# mpiv2.net
KiCad netlist of a schematic drawn in EAGLE
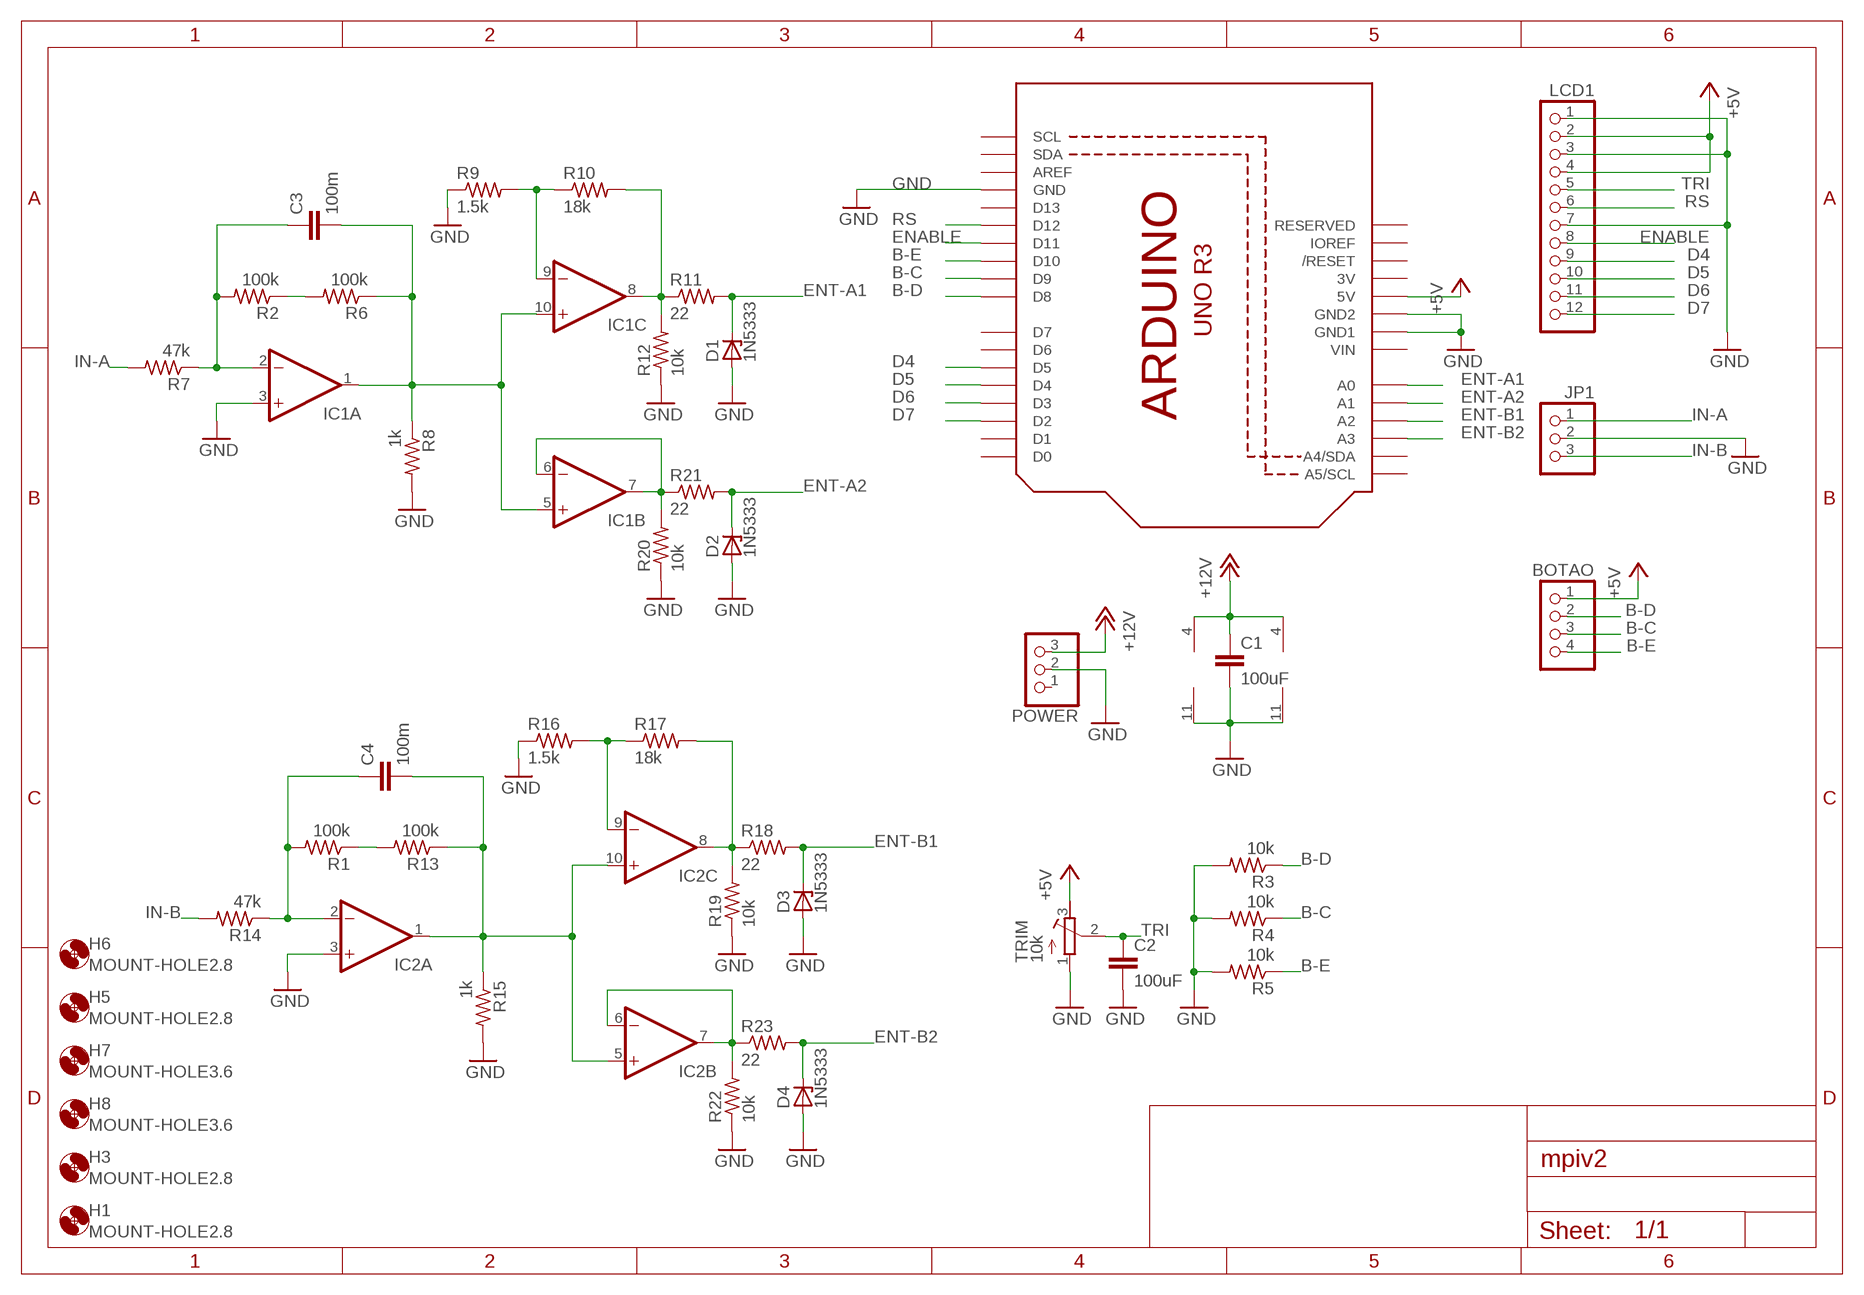
[diagram p0: schematic, sheet 1]

(export (version "E")
  (design (tool "Eeschema 10.0.6"))
  (components
    (comp (ref "BOTAO")
      (value "HEADER-1X4")
      (footprint "eagle-import:1X04_OVAL")
      (libsource (lib "eagle-import") (part "HEADER-1X4"))
    )
    (comp (ref "C1")
      (value "100uF")
      (footprint "eagle-import:C050-035X075")
      (libsource (lib "eagle-import") (part "C-EU050-035X075"))
    )
    (comp (ref "C2")
      (value "100uF")
      (footprint "eagle-import:C050-035X075")
      (libsource (lib "eagle-import") (part "C-EU050-035X075"))
    )
    (comp (ref "C3")
      (value "100m")
      (footprint "eagle-import:C075-032X103")
      (libsource (lib "eagle-import") (part "C-EU075-032X103"))
    )
    (comp (ref "C4")
      (value "100m")
      (footprint "eagle-import:C075-032X103")
      (libsource (lib "eagle-import") (part "C-EU075-032X103"))
    )
    (comp (ref "D1")
      (value "1N5333")
      (footprint "eagle-import:C1702-15")
      (libsource (lib "eagle-import") (part "1N5333"))
    )
    (comp (ref "D2")
      (value "1N5333")
      (footprint "eagle-import:C1702-15")
      (libsource (lib "eagle-import") (part "1N5333"))
    )
    (comp (ref "D3")
      (value "1N5333")
      (footprint "eagle-import:C1702-15")
      (libsource (lib "eagle-import") (part "1N5333"))
    )
    (comp (ref "D4")
      (value "1N5333")
      (footprint "eagle-import:C1702-15")
      (libsource (lib "eagle-import") (part "1N5333"))
    )
    (comp (ref "H1")
      (value "MOUNT-HOLE2.8")
      (footprint "eagle-import:2,8")
      (libsource (lib "eagle-import") (part "MOUNT-HOLE2.8"))
    )
    (comp (ref "H3")
      (value "MOUNT-HOLE2.8")
      (footprint "eagle-import:2,8")
      (libsource (lib "eagle-import") (part "MOUNT-HOLE2.8"))
    )
    (comp (ref "H5")
      (value "MOUNT-HOLE2.8")
      (footprint "eagle-import:2,8")
      (libsource (lib "eagle-import") (part "MOUNT-HOLE2.8"))
    )
    (comp (ref "H6")
      (value "MOUNT-HOLE2.8")
      (footprint "eagle-import:2,8")
      (libsource (lib "eagle-import") (part "MOUNT-HOLE2.8"))
    )
    (comp (ref "H7")
      (value "MOUNT-HOLE3.6")
      (footprint "eagle-import:3,6")
      (libsource (lib "eagle-import") (part "MOUNT-HOLE3.6"))
    )
    (comp (ref "H8")
      (value "MOUNT-HOLE3.6")
      (footprint "eagle-import:3,6")
      (libsource (lib "eagle-import") (part "MOUNT-HOLE3.6"))
    )
    (comp (ref "IC1")
      (value "4AMP_P4+11N")
      (footprint "eagle-import:DIL14")
      (libsource (lib "eagle-import") (part "4AMP_P4+11N"))
    )
    (comp (ref "IC2")
      (value "4AMP_P4+11N")
      (footprint "eagle-import:DIL14")
      (libsource (lib "eagle-import") (part "4AMP_P4+11N"))
    )
    (comp (ref "JP1")
      (value "PINHD-1X3")
      (footprint "eagle-import:1X03")
      (libsource (lib "eagle-import") (part "PINHD-1X3"))
    )
    (comp (ref "LCD1")
      (value "PINHD-1X12")
      (footprint "eagle-import:1X12")
      (libsource (lib "eagle-import") (part "PINHD-1X12"))
    )
    (comp (ref "POWER")
      (value "HEADER-1X3")
      (footprint "eagle-import:1X03_OVAL")
      (libsource (lib "eagle-import") (part "HEADER-1X3"))
    )
    (comp (ref "R1")
      (value "100k")
      (footprint "eagle-import:0207_10")
      (libsource (lib "eagle-import") (part "R-US_0207/10"))
    )
    (comp (ref "R2")
      (value "100k")
      (footprint "eagle-import:0207_10")
      (libsource (lib "eagle-import") (part "R-US_0207/10"))
    )
    (comp (ref "R3")
      (value "10k")
      (footprint "eagle-import:0207_10")
      (libsource (lib "eagle-import") (part "R-US_0207/10"))
    )
    (comp (ref "R4")
      (value "10k")
      (footprint "eagle-import:0207_10")
      (libsource (lib "eagle-import") (part "R-US_0207/10"))
    )
    (comp (ref "R5")
      (value "10k")
      (footprint "eagle-import:0207_10")
      (libsource (lib "eagle-import") (part "R-US_0207/10"))
    )
    (comp (ref "R6")
      (value "100k")
      (footprint "eagle-import:0207_10")
      (libsource (lib "eagle-import") (part "R-US_0207/10"))
    )
    (comp (ref "R7")
      (value "47k")
      (footprint "eagle-import:0207_10")
      (libsource (lib "eagle-import") (part "R-US_0207/10"))
    )
    (comp (ref "R8")
      (value "1k")
      (footprint "eagle-import:0207_10")
      (libsource (lib "eagle-import") (part "R-US_0207/10"))
    )
    (comp (ref "R9")
      (value "1.5k")
      (footprint "eagle-import:0207_10")
      (libsource (lib "eagle-import") (part "R-US_0207/10"))
    )
    (comp (ref "R10")
      (value "18k")
      (footprint "eagle-import:0207_10")
      (libsource (lib "eagle-import") (part "R-US_0207/10"))
    )
    (comp (ref "R11")
      (value "22")
      (footprint "eagle-import:0207_10")
      (libsource (lib "eagle-import") (part "R-US_0207/10"))
    )
    (comp (ref "R12")
      (value "10k")
      (footprint "eagle-import:0207_10")
      (libsource (lib "eagle-import") (part "R-US_0207/10"))
    )
    (comp (ref "R13")
      (value "100k")
      (footprint "eagle-import:0207_10")
      (libsource (lib "eagle-import") (part "R-US_0207/10"))
    )
    (comp (ref "R14")
      (value "47k")
      (footprint "eagle-import:0207_10")
      (libsource (lib "eagle-import") (part "R-US_0207/10"))
    )
    (comp (ref "R15")
      (value "1k")
      (footprint "eagle-import:0207_10")
      (libsource (lib "eagle-import") (part "R-US_0207/10"))
    )
    (comp (ref "R16")
      (value "1.5k")
      (footprint "eagle-import:0207_10")
      (libsource (lib "eagle-import") (part "R-US_0207/10"))
    )
    (comp (ref "R17")
      (value "18k")
      (footprint "eagle-import:0207_10")
      (libsource (lib "eagle-import") (part "R-US_0207/10"))
    )
    (comp (ref "R18")
      (value "22")
      (footprint "eagle-import:0207_10")
      (libsource (lib "eagle-import") (part "R-US_0207/10"))
    )
    (comp (ref "R19")
      (value "10k")
      (footprint "eagle-import:0207_10")
      (libsource (lib "eagle-import") (part "R-US_0207/10"))
    )
    (comp (ref "R20")
      (value "10k")
      (footprint "eagle-import:0207_10")
      (libsource (lib "eagle-import") (part "R-US_0207/10"))
    )
    (comp (ref "R21")
      (value "22")
      (footprint "eagle-import:0207_10")
      (libsource (lib "eagle-import") (part "R-US_0207/10"))
    )
    (comp (ref "R22")
      (value "10k")
      (footprint "eagle-import:0207_10")
      (libsource (lib "eagle-import") (part "R-US_0207/10"))
    )
    (comp (ref "R23")
      (value "22")
      (footprint "eagle-import:0207_10")
      (libsource (lib "eagle-import") (part "R-US_0207/10"))
    )
    (comp (ref "TRIM")
      (value "10k")
      (footprint "eagle-import:RTRIM74W")
      (libsource (lib "eagle-import") (part "R-TRIMM74W"))
    )
    (comp (ref "U1")
      (value "ARDUINOR3-BPLACE")
      (footprint "eagle-import:ARDUINOR3-BPLACE")
      (libsource (lib "eagle-import") (part "ARDUINOR3-BPLACE"))
    )
  )
  (nets
    (net (code "1") (name "+5V") (class "Default")
      (node (ref "BOTAO") (pin "1") (pinfunction "1_1") (pintype "passive"))
      (node (ref "LCD1") (pin "2") (pinfunction "2_2") (pintype "passive"))
      (node (ref "LCD1") (pin "4") (pinfunction "4_4") (pintype "passive"))
      (node (ref "TRIM") (pin "3") (pinfunction "A_3") (pintype "passive"))
      (node (ref "U1") (pin "5V") (pinfunction "5V_5V") (pintype "power_in"))
    )
    (net (code "2") (name "+12V") (class "Default")
      (node (ref "C1") (pin "1") (pinfunction "1_1") (pintype "passive"))
      (node (ref "IC1") (pin "4") (pinfunction "V+_4") (pintype "power_in"))
      (node (ref "IC2") (pin "4") (pinfunction "V+_4") (pintype "power_in"))
      (node (ref "POWER") (pin "3") (pinfunction "3_3") (pintype "passive"))
    )
    (net (code "3") (name "/3V") (class "Default")
      (node (ref "U1") (pin "3V") (pinfunction "3V_3V") (pintype "power_in"))
    )
    (net (code "4") (name "/B-C") (class "Default")
      (node (ref "BOTAO") (pin "3") (pinfunction "3_3") (pintype "passive"))
      (node (ref "R4") (pin "1") (pinfunction "1_1") (pintype "passive"))
      (node (ref "U1") (pin "D9") (pinfunction "D9_D9") (pintype "bidirectional"))
    )
    (net (code "5") (name "/B-D") (class "Default")
      (node (ref "BOTAO") (pin "2") (pinfunction "2_2") (pintype "passive"))
      (node (ref "R3") (pin "1") (pinfunction "1_1") (pintype "passive"))
      (node (ref "U1") (pin "D8") (pinfunction "D8_D8") (pintype "bidirectional"))
    )
    (net (code "6") (name "/B-E") (class "Default")
      (node (ref "BOTAO") (pin "4") (pinfunction "4_4") (pintype "passive"))
      (node (ref "R5") (pin "1") (pinfunction "1_1") (pintype "passive"))
      (node (ref "U1") (pin "D10") (pinfunction "D10_D10") (pintype "bidirectional"))
    )
    (net (code "7") (name "/D4") (class "Default")
      (node (ref "LCD1") (pin "9") (pinfunction "9_9") (pintype "passive"))
      (node (ref "U1") (pin "D5") (pinfunction "D5_D5") (pintype "bidirectional"))
    )
    (net (code "8") (name "/D5") (class "Default")
      (node (ref "LCD1") (pin "10") (pinfunction "10_10") (pintype "passive"))
      (node (ref "U1") (pin "D4") (pinfunction "D4_D4") (pintype "bidirectional"))
    )
    (net (code "9") (name "/D6") (class "Default")
      (node (ref "LCD1") (pin "11") (pinfunction "11_11") (pintype "passive"))
      (node (ref "U1") (pin "D3") (pinfunction "D3_D3") (pintype "bidirectional"))
    )
    (net (code "10") (name "/D7") (class "Default")
      (node (ref "LCD1") (pin "12") (pinfunction "12_12") (pintype "passive"))
      (node (ref "U1") (pin "D2") (pinfunction "D2_D2") (pintype "bidirectional"))
    )
    (net (code "11") (name "/ENABLE") (class "Default")
      (node (ref "LCD1") (pin "8") (pinfunction "8_8") (pintype "passive"))
      (node (ref "U1") (pin "D11") (pinfunction "D11_D11") (pintype "bidirectional"))
    )
    (net (code "12") (name "/ENT-A1") (class "Default")
      (node (ref "D1") (pin "C") (pinfunction "C_C") (pintype "passive"))
      (node (ref "R11") (pin "2") (pinfunction "2_2") (pintype "passive"))
      (node (ref "U1") (pin "A0") (pinfunction "A0_A0") (pintype "bidirectional"))
    )
    (net (code "13") (name "/ENT-A2") (class "Default")
      (node (ref "D2") (pin "C") (pinfunction "C_C") (pintype "passive"))
      (node (ref "R21") (pin "2") (pinfunction "2_2") (pintype "passive"))
      (node (ref "U1") (pin "A1") (pinfunction "A1_A1") (pintype "bidirectional"))
    )
    (net (code "14") (name "/ENT-B1") (class "Default")
      (node (ref "D3") (pin "C") (pinfunction "C_C") (pintype "passive"))
      (node (ref "R18") (pin "2") (pinfunction "2_2") (pintype "passive"))
      (node (ref "U1") (pin "A2") (pinfunction "A2_A2") (pintype "bidirectional"))
    )
    (net (code "15") (name "/ENT-B2") (class "Default")
      (node (ref "D4") (pin "C") (pinfunction "C_C") (pintype "passive"))
      (node (ref "R23") (pin "2") (pinfunction "2_2") (pintype "passive"))
      (node (ref "U1") (pin "A3") (pinfunction "A3_A3") (pintype "bidirectional"))
    )
    (net (code "16") (name "/IN-A") (class "Default")
      (node (ref "JP1") (pin "1") (pinfunction "1_1") (pintype "passive"))
      (node (ref "R7") (pin "2") (pinfunction "2_2") (pintype "passive"))
    )
    (net (code "17") (name "/IN-B") (class "Default")
      (node (ref "JP1") (pin "3") (pinfunction "3_3") (pintype "passive"))
      (node (ref "R14") (pin "2") (pinfunction "2_2") (pintype "passive"))
    )
    (net (code "18") (name "/RS") (class "Default")
      (node (ref "LCD1") (pin "6") (pinfunction "6_6") (pintype "passive"))
      (node (ref "U1") (pin "D12") (pinfunction "D12_D12") (pintype "bidirectional"))
    )
    (net (code "19") (name "/TRI") (class "Default")
      (node (ref "C2") (pin "1") (pinfunction "1_1") (pintype "passive"))
      (node (ref "LCD1") (pin "5") (pinfunction "5_5") (pintype "passive"))
      (node (ref "TRIM") (pin "2") (pinfunction "S_2") (pintype "passive"))
    )
    (net (code "20") (name "/VIN") (class "Default")
      (node (ref "U1") (pin "VIN") (pinfunction "VIN_VIN") (pintype "power_in"))
    )
    (net (code "21") (name "GND") (class "Default")
      (node (ref "C1") (pin "2") (pinfunction "2_2") (pintype "passive"))
      (node (ref "C2") (pin "2") (pinfunction "2_2") (pintype "passive"))
      (node (ref "D1") (pin "A") (pinfunction "A_A") (pintype "passive"))
      (node (ref "D2") (pin "A") (pinfunction "A_A") (pintype "passive"))
      (node (ref "D3") (pin "A") (pinfunction "A_A") (pintype "passive"))
      (node (ref "D4") (pin "A") (pinfunction "A_A") (pintype "passive"))
      (node (ref "IC1") (pin "11") (pinfunction "V-_11") (pintype "power_in"))
      (node (ref "IC1") (pin "3") (pinfunction "+IN_3") (pintype "input"))
      (node (ref "IC2") (pin "11") (pinfunction "V-_11") (pintype "power_in"))
      (node (ref "IC2") (pin "3") (pinfunction "+IN_3") (pintype "input"))
      (node (ref "JP1") (pin "2") (pinfunction "2_2") (pintype "passive"))
      (node (ref "LCD1") (pin "1") (pinfunction "1_1") (pintype "passive"))
      (node (ref "LCD1") (pin "3") (pinfunction "3_3") (pintype "passive"))
      (node (ref "LCD1") (pin "7") (pinfunction "7_7") (pintype "passive"))
      (node (ref "POWER") (pin "2") (pinfunction "2_2") (pintype "passive"))
      (node (ref "R12") (pin "1") (pinfunction "1_1") (pintype "passive"))
      (node (ref "R15") (pin "2") (pinfunction "2_2") (pintype "passive"))
      (node (ref "R16") (pin "1") (pinfunction "1_1") (pintype "passive"))
      (node (ref "R19") (pin "1") (pinfunction "1_1") (pintype "passive"))
      (node (ref "R20") (pin "1") (pinfunction "1_1") (pintype "passive"))
      (node (ref "R22") (pin "1") (pinfunction "1_1") (pintype "passive"))
      (node (ref "R3") (pin "2") (pinfunction "2_2") (pintype "passive"))
      (node (ref "R4") (pin "2") (pinfunction "2_2") (pintype "passive"))
      (node (ref "R5") (pin "2") (pinfunction "2_2") (pintype "passive"))
      (node (ref "R8") (pin "2") (pinfunction "2_2") (pintype "passive"))
      (node (ref "R9") (pin "1") (pinfunction "1_1") (pintype "passive"))
      (node (ref "TRIM") (pin "1") (pinfunction "E_1") (pintype "passive"))
      (node (ref "U1") (pin "GND") (pinfunction "GND_GND") (pintype "power_in"))
      (node (ref "U1") (pin "GND1") (pinfunction "GND1_GND1") (pintype "power_in"))
      (node (ref "U1") (pin "GND2") (pinfunction "GND2_GND2") (pintype "power_in"))
    )
    (net (code "22") (name "Net-(IC1A--IN)") (class "Default")
      (node (ref "C3") (pin "1") (pinfunction "1_1") (pintype "passive"))
      (node (ref "IC1") (pin "2") (pinfunction "-IN_2") (pintype "input"))
      (node (ref "R2") (pin "2") (pinfunction "2_2") (pintype "passive"))
      (node (ref "R7") (pin "1") (pinfunction "1_1") (pintype "passive"))
    )
    (net (code "23") (name "Net-(IC1A-OUT)") (class "Default")
      (node (ref "C3") (pin "2") (pinfunction "2_2") (pintype "passive"))
      (node (ref "IC1") (pin "1") (pinfunction "OUT_1") (pintype "output"))
      (node (ref "IC1") (pin "10") (pinfunction "+IN_10") (pintype "input"))
      (node (ref "IC1") (pin "5") (pinfunction "+IN_5") (pintype "input"))
      (node (ref "R6") (pin "1") (pinfunction "1_1") (pintype "passive"))
      (node (ref "R8") (pin "1") (pinfunction "1_1") (pintype "passive"))
    )
    (net (code "24") (name "Net-(IC1B--IN)") (class "Default")
      (node (ref "IC1") (pin "6") (pinfunction "-IN_6") (pintype "input"))
      (node (ref "IC1") (pin "7") (pinfunction "OUT_7") (pintype "output"))
      (node (ref "R20") (pin "2") (pinfunction "2_2") (pintype "passive"))
      (node (ref "R21") (pin "1") (pinfunction "1_1") (pintype "passive"))
    )
    (net (code "25") (name "Net-(IC1C--IN)") (class "Default")
      (node (ref "IC1") (pin "9") (pinfunction "-IN_9") (pintype "input"))
      (node (ref "R10") (pin "1") (pinfunction "1_1") (pintype "passive"))
      (node (ref "R9") (pin "2") (pinfunction "2_2") (pintype "passive"))
    )
    (net (code "26") (name "Net-(IC1C-OUT)") (class "Default")
      (node (ref "IC1") (pin "8") (pinfunction "OUT_8") (pintype "output"))
      (node (ref "R10") (pin "2") (pinfunction "2_2") (pintype "passive"))
      (node (ref "R11") (pin "1") (pinfunction "1_1") (pintype "passive"))
      (node (ref "R12") (pin "2") (pinfunction "2_2") (pintype "passive"))
    )
    (net (code "27") (name "Net-(IC2A--IN)") (class "Default")
      (node (ref "C4") (pin "1") (pinfunction "1_1") (pintype "passive"))
      (node (ref "IC2") (pin "2") (pinfunction "-IN_2") (pintype "input"))
      (node (ref "R1") (pin "2") (pinfunction "2_2") (pintype "passive"))
      (node (ref "R14") (pin "1") (pinfunction "1_1") (pintype "passive"))
    )
    (net (code "28") (name "Net-(IC2A-OUT)") (class "Default")
      (node (ref "C4") (pin "2") (pinfunction "2_2") (pintype "passive"))
      (node (ref "IC2") (pin "1") (pinfunction "OUT_1") (pintype "output"))
      (node (ref "IC2") (pin "10") (pinfunction "+IN_10") (pintype "input"))
      (node (ref "IC2") (pin "5") (pinfunction "+IN_5") (pintype "input"))
      (node (ref "R13") (pin "1") (pinfunction "1_1") (pintype "passive"))
      (node (ref "R15") (pin "1") (pinfunction "1_1") (pintype "passive"))
    )
    (net (code "29") (name "Net-(IC2B--IN)") (class "Default")
      (node (ref "IC2") (pin "6") (pinfunction "-IN_6") (pintype "input"))
      (node (ref "IC2") (pin "7") (pinfunction "OUT_7") (pintype "output"))
      (node (ref "R22") (pin "2") (pinfunction "2_2") (pintype "passive"))
      (node (ref "R23") (pin "1") (pinfunction "1_1") (pintype "passive"))
    )
    (net (code "30") (name "Net-(IC2C--IN)") (class "Default")
      (node (ref "IC2") (pin "9") (pinfunction "-IN_9") (pintype "input"))
      (node (ref "R16") (pin "2") (pinfunction "2_2") (pintype "passive"))
      (node (ref "R17") (pin "1") (pinfunction "1_1") (pintype "passive"))
    )
    (net (code "31") (name "Net-(IC2C-OUT)") (class "Default")
      (node (ref "IC2") (pin "8") (pinfunction "OUT_8") (pintype "output"))
      (node (ref "R17") (pin "2") (pinfunction "2_2") (pintype "passive"))
      (node (ref "R18") (pin "1") (pinfunction "1_1") (pintype "passive"))
      (node (ref "R19") (pin "2") (pinfunction "2_2") (pintype "passive"))
    )
    (net (code "32") (name "Net-(R1-Pad1)") (class "Default")
      (node (ref "R1") (pin "1") (pinfunction "1_1") (pintype "passive"))
      (node (ref "R13") (pin "2") (pinfunction "2_2") (pintype "passive"))
    )
    (net (code "33") (name "Net-(R2-Pad1)") (class "Default")
      (node (ref "R2") (pin "1") (pinfunction "1_1") (pintype "passive"))
      (node (ref "R6") (pin "2") (pinfunction "2_2") (pintype "passive"))
    )
    (net (code "34") (name "unconnected-(POWER-Pad1)") (class "Default")
      (node (ref "POWER") (pin "1") (pinfunction "1_1") (pintype "passive"))
    )
    (net (code "35") (name "unconnected-(U1-A4{slash}SDA-PadA4)") (class "Default")
      (node (ref "U1") (pin "A4") (pinfunction "A4/SDA_A4") (pintype "bidirectional"))
    )
    (net (code "36") (name "unconnected-(U1-A5{slash}SCL-PadA5)") (class "Default")
      (node (ref "U1") (pin "A5") (pinfunction "A5/SCL_A5") (pintype "bidirectional"))
    )
    (net (code "37") (name "unconnected-(U1-PadAREF)") (class "Default")
      (node (ref "U1") (pin "AREF") (pinfunction "AREF_AREF") (pintype "bidirectional"))
    )
    (net (code "38") (name "unconnected-(U1-PadD0)") (class "Default")
      (node (ref "U1") (pin "D0") (pinfunction "D0_D0") (pintype "bidirectional"))
    )
    (net (code "39") (name "unconnected-(U1-PadD1)") (class "Default")
      (node (ref "U1") (pin "D1") (pinfunction "D1_D1") (pintype "bidirectional"))
    )
    (net (code "40") (name "unconnected-(U1-PadD6)") (class "Default")
      (node (ref "U1") (pin "D6") (pinfunction "D6_D6") (pintype "bidirectional"))
    )
    (net (code "41") (name "unconnected-(U1-PadD7)") (class "Default")
      (node (ref "U1") (pin "D7") (pinfunction "D7_D7") (pintype "bidirectional"))
    )
    (net (code "42") (name "unconnected-(U1-PadD13)") (class "Default")
      (node (ref "U1") (pin "D13") (pinfunction "D13_D13") (pintype "bidirectional"))
    )
    (net (code "43") (name "unconnected-(U1-PadIOREF)") (class "Default")
      (node (ref "U1") (pin "IOREF") (pinfunction "IOREF_IOREF") (pintype "output"))
    )
    (net (code "44") (name "unconnected-(U1-PadRESERVED)") (class "Default")
      (node (ref "U1") (pin "RESERVED") (pinfunction "RESERVED_RESERVED") (pintype "no_connect"))
    )
    (net (code "45") (name "unconnected-(U1-PadSCL)") (class "Default")
      (node (ref "U1") (pin "SCL") (pinfunction "SCL_SCL") (pintype "bidirectional"))
    )
    (net (code "46") (name "unconnected-(U1-PadSDA)") (class "Default")
      (node (ref "U1") (pin "SDA") (pinfunction "SDA_SDA") (pintype "bidirectional"))
    )
    (net (code "47") (name "unconnected-(U1-{slash}RESET-PadRESET)") (class "Default")
      (node (ref "U1") (pin "RESET") (pinfunction "/RESET_RESET") (pintype "bidirectional"))
    )
  )
)
